# PG03_Analog_Digital_Inputs.net
KiCad netlist of a schematic drawn in Altium Designer
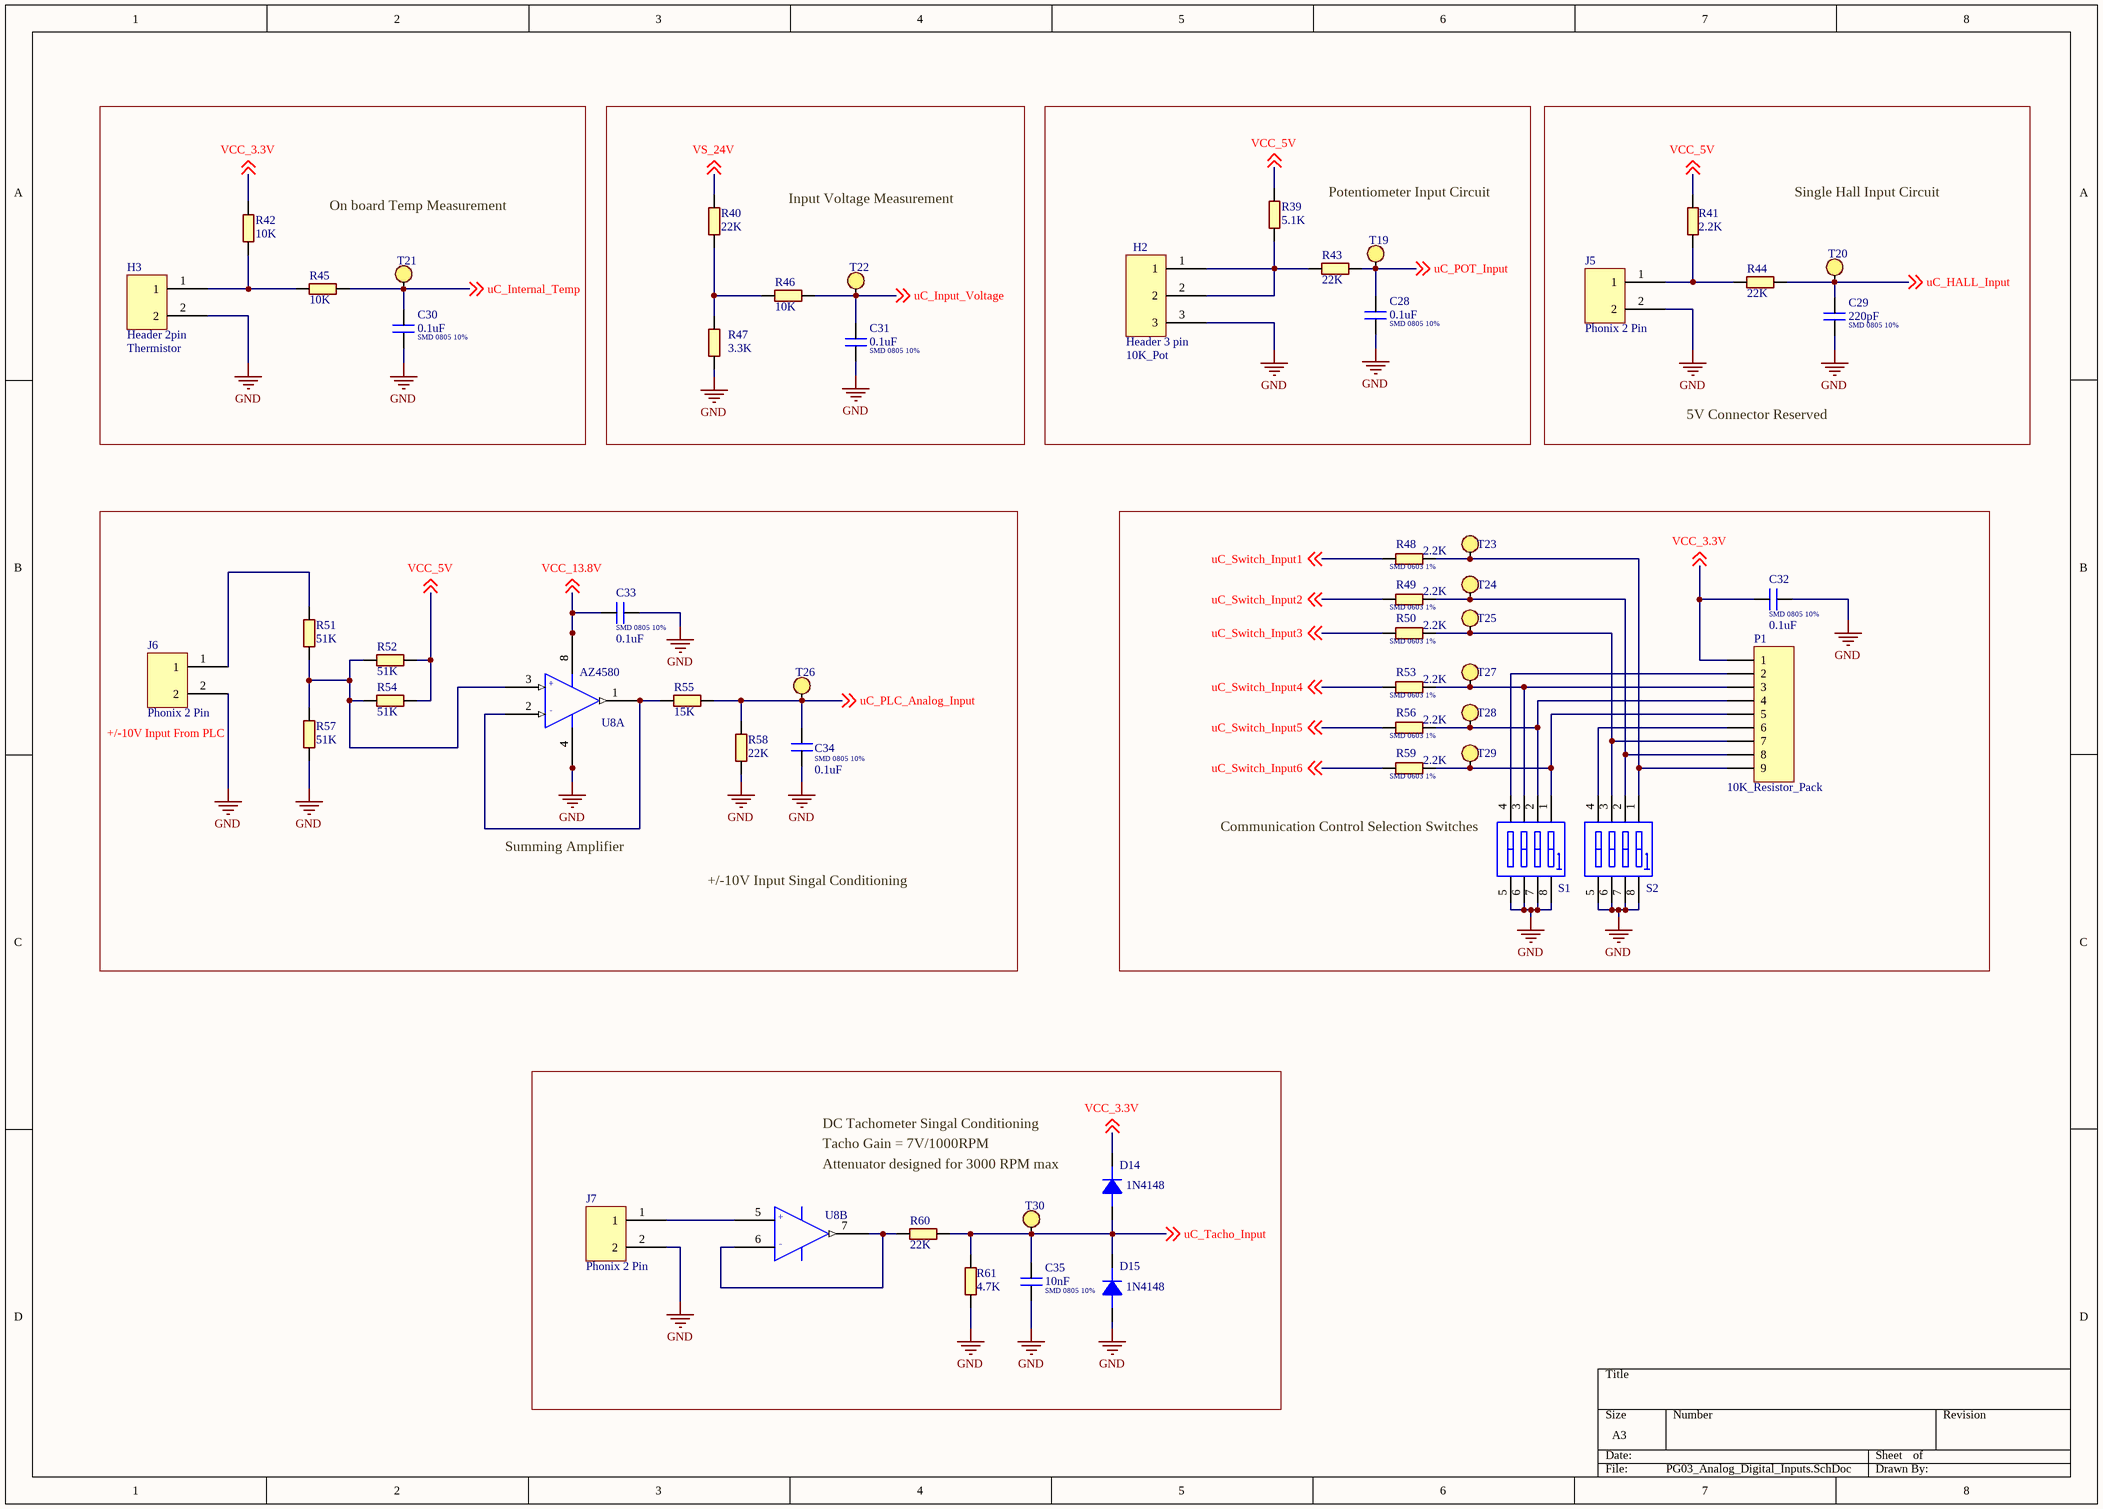
[diagram p0: PG03_Analog_Digital_Inputs.SchDoc]

(export (version "E")
  (design (tool "Eeschema 10.0.6"))
  (components
    (comp (ref "C28")
      (value "SMD 0805 10%")
      (footprint "SMD0805")
      (fields (field (name "MANUFACTURER") "Vishay") (field (name "ALTIUM_VALUE") "0.1uF"))
      (libsource (lib "Schlib1") (part "CAP_SMD"))
    )
    (comp (ref "C29")
      (value "SMD 0805 10%")
      (footprint "SMD0805")
      (fields (field (name "MANUFACTURER") "Vishay") (field (name "ALTIUM_VALUE") "220pF"))
      (libsource (lib "Schlib1") (part "CAP_SMD"))
    )
    (comp (ref "C30")
      (value "SMD 0805 10%")
      (footprint "SMD0805")
      (fields (field (name "MANUFACTURER") "Vishay") (field (name "ALTIUM_VALUE") "0.1uF"))
      (libsource (lib "Schlib1") (part "CAP_SMD"))
    )
    (comp (ref "C31")
      (value "SMD 0805 10%")
      (footprint "SMD0805")
      (fields (field (name "MANUFACTURER") "Vishay") (field (name "ALTIUM_VALUE") "0.1uF"))
      (libsource (lib "Schlib1") (part "CAP_SMD"))
    )
    (comp (ref "C32")
      (value "SMD 0805 10%")
      (footprint "SMD0805")
      (fields (field (name "MANUFACTURER") "Vishay") (field (name "ALTIUM_VALUE") "0.1uF"))
      (libsource (lib "Schlib1") (part "CAP_SMD"))
    )
    (comp (ref "C33")
      (value "SMD 0805 10%")
      (footprint "SMD0805")
      (fields (field (name "MANUFACTURER") "Vishay") (field (name "ALTIUM_VALUE") "0.1uF"))
      (libsource (lib "Schlib1") (part "CAP_SMD"))
    )
    (comp (ref "C34")
      (value "SMD 0805 10%")
      (footprint "SMD0805")
      (fields (field (name "MANUFACTURER") "Vishay") (field (name "ALTIUM_VALUE") "0.1uF"))
      (libsource (lib "Schlib1") (part "CAP_SMD"))
    )
    (comp (ref "C35")
      (value "SMD 0805 10%")
      (footprint "SMD0805")
      (fields (field (name "MANUFACTURER") "Vishay") (field (name "ALTIUM_VALUE") "10nF"))
      (libsource (lib "Schlib1") (part "CAP_SMD"))
    )
    (comp (ref "D14")
      (value "1N4148")
      (fields
        (field (name "PART NO.") "SM4007")
        (field (name "TOLERANCE") "10%")
        (field (name "MANUFACTURER") "Vishay")
      )
      (libsource (lib "*") (part "1N4148"))
    )
    (comp (ref "D15")
      (value "1N4148")
      (fields
        (field (name "PART NO.") "SM4007")
        (field (name "TOLERANCE") "10%")
        (field (name "MANUFACTURER") "Vishay")
      )
      (libsource (lib "*") (part "1N4148"))
    )
    (comp (ref "H2")
      (value "10K_Pot")
      (footprint "Header-3-Pin")
      (fields (field (name "ALTIUM_VALUE") "Header 3 pin"))
      (libsource (lib "Schlib1") (part "Header_3_Pin"))
    )
    (comp (ref "H3")
      (value "Thermistor")
      (footprint "Header-2-Pin")
      (fields (field (name "ALTIUM_VALUE") "Header 2pin"))
      (libsource (lib "Schlib1") (part "Header_2_Pin"))
    )
    (comp (ref "J5")
      (value "Phonix 2 Pin")
      (footprint "PHONIX2")
      (libsource (lib "Schlib1") (part "Phonix_2_Pin"))
    )
    (comp (ref "J6")
      (value "Phonix 2 Pin")
      (footprint "PHONIX2")
      (libsource (lib "Schlib1") (part "Phonix_2_Pin"))
    )
    (comp (ref "J7")
      (value "Phonix 2 Pin")
      (footprint "PHONIX2")
      (libsource (lib "Schlib1") (part "Phonix_2_Pin"))
    )
    (comp (ref "P1")
      (value "10K_Resistor_Pack")
      (footprint "HDR1X9")
      (description "Header, 9-Pin")
      (fields (field (name "PUBLISHER") "Altium Limited"))
      (libsource (lib "Miscellaneous Connectors") (part "Header 9"))
    )
    (comp (ref "R39")
      (value "5.1K")
      (footprint "SMD1206")
      (description "SMD1206  1% Resistor")
      (fields (field (name "MANUFACTURER") "Vishay") (field (name "Comment") "SMD 1206 1%"))
      (libsource (lib "") (part "RES_SMD_1"))
    )
    (comp (ref "R40")
      (value "22K")
      (footprint "SMD1206")
      (description "SMD1206  1% Resistor")
      (fields (field (name "MANUFACTURER") "Vishay") (field (name "Comment") "SMD 1206 1%"))
      (libsource (lib "") (part "RES_SMD_1"))
    )
    (comp (ref "R41")
      (value "2.2K")
      (footprint "SMD1206")
      (description "SMD1206  1% Resistor")
      (fields (field (name "MANUFACTURER") "Vishay") (field (name "Comment") "SMD 1206 1%"))
      (libsource (lib "") (part "RES_SMD_3"))
    )
    (comp (ref "R42")
      (value "10K")
      (footprint "SMD1206")
      (description "SMD1206  1% Resistor")
      (fields (field (name "MANUFACTURER") "Vishay") (field (name "Comment") "SMD 1206 1%"))
      (libsource (lib "") (part "RES_SMD_1"))
    )
    (comp (ref "R43")
      (value "22K")
      (footprint "SMD1206")
      (description "SMD1206  1% Resistor")
      (fields (field (name "MANUFACTURER") "Vishay") (field (name "Comment") "SMD 1206 1%"))
      (libsource (lib "") (part "RES_SMD_2"))
    )
    (comp (ref "R44")
      (value "22K")
      (footprint "SMD1206")
      (description "SMD1206  1% Resistor")
      (fields (field (name "MANUFACTURER") "Vishay") (field (name "Comment") "SMD 1206 1%"))
      (libsource (lib "") (part "RES_SMD_2"))
    )
    (comp (ref "R45")
      (value "10K")
      (footprint "SMD1206")
      (description "SMD1206  1% Resistor")
      (fields (field (name "MANUFACTURER") "Vishay") (field (name "Comment") "SMD 1206 1%"))
      (libsource (lib "") (part "RES_SMD_2"))
    )
    (comp (ref "R46")
      (value "10K")
      (footprint "SMD1206")
      (description "SMD1206  1% Resistor")
      (fields (field (name "MANUFACTURER") "Vishay") (field (name "Comment") "SMD 1206 1%"))
      (libsource (lib "") (part "RES_SMD_2"))
    )
    (comp (ref "R47")
      (value "3.3K")
      (footprint "SMD1206")
      (description "SMD1206  1% Resistor")
      (fields (field (name "MANUFACTURER") "Vishay") (field (name "Comment") "SMD 1206 1%"))
      (libsource (lib "") (part "RES_SMD_3"))
    )
    (comp (ref "R48")
      (value "SMD 0603 1%")
      (footprint "SMD0603")
      (description "SMD1206  1% Resistor")
      (fields (field (name "MANUFACTURER") "Vishay") (field (name "ALTIUM_VALUE") "2.2K"))
      (libsource (lib "Schlib1") (part "RES_SMD"))
    )
    (comp (ref "R49")
      (value "SMD 0603 1%")
      (footprint "SMD0603")
      (description "SMD1206  1% Resistor")
      (fields (field (name "MANUFACTURER") "Vishay") (field (name "ALTIUM_VALUE") "2.2K"))
      (libsource (lib "Schlib1") (part "RES_SMD"))
    )
    (comp (ref "R50")
      (value "SMD 0603 1%")
      (footprint "SMD0603")
      (description "SMD1206  1% Resistor")
      (fields (field (name "MANUFACTURER") "Vishay") (field (name "ALTIUM_VALUE") "2.2K"))
      (libsource (lib "Schlib1") (part "RES_SMD"))
    )
    (comp (ref "R51")
      (value "51K")
      (footprint "SMD1206")
      (description "SMD1206  1% Resistor")
      (fields (field (name "MANUFACTURER") "Vishay") (field (name "Comment") "SMD 1206 1%"))
      (libsource (lib "") (part "RES_SMD_1"))
    )
    (comp (ref "R52")
      (value "51K")
      (footprint "SMD1206")
      (description "SMD1206  1% Resistor")
      (fields (field (name "MANUFACTURER") "Vishay") (field (name "Comment") "SMD 1206 1%"))
      (libsource (lib "") (part "RES_SMD_2"))
    )
    (comp (ref "R53")
      (value "SMD 0603 1%")
      (footprint "SMD0603")
      (description "SMD1206  1% Resistor")
      (fields (field (name "MANUFACTURER") "Vishay") (field (name "ALTIUM_VALUE") "2.2K"))
      (libsource (lib "Schlib1") (part "RES_SMD"))
    )
    (comp (ref "R54")
      (value "51K")
      (footprint "SMD1206")
      (description "SMD1206  1% Resistor")
      (fields (field (name "MANUFACTURER") "Vishay") (field (name "Comment") "SMD 1206 1%"))
      (libsource (lib "") (part "RES_SMD_2"))
    )
    (comp (ref "R55")
      (value "15K")
      (footprint "SMD1206")
      (description "SMD1206  1% Resistor")
      (fields (field (name "MANUFACTURER") "Vishay") (field (name "Comment") "SMD 1206 1%"))
      (libsource (lib "") (part "RES_SMD_2"))
    )
    (comp (ref "R56")
      (value "SMD 0603 1%")
      (footprint "SMD0603")
      (description "SMD1206  1% Resistor")
      (fields (field (name "MANUFACTURER") "Vishay") (field (name "ALTIUM_VALUE") "2.2K"))
      (libsource (lib "Schlib1") (part "RES_SMD"))
    )
    (comp (ref "R57")
      (value "51K")
      (footprint "SMD1206")
      (description "SMD1206  1% Resistor")
      (fields (field (name "MANUFACTURER") "Vishay") (field (name "Comment") "SMD 1206 1%"))
      (libsource (lib "") (part "RES_SMD_1"))
    )
    (comp (ref "R58")
      (value "22K")
      (footprint "SMD1206")
      (description "SMD1206  1% Resistor")
      (fields (field (name "MANUFACTURER") "Vishay") (field (name "Comment") "SMD 1206 1%"))
      (libsource (lib "") (part "RES_SMD_1"))
    )
    (comp (ref "R59")
      (value "SMD 0603 1%")
      (footprint "SMD0603")
      (description "SMD1206  1% Resistor")
      (fields (field (name "MANUFACTURER") "Vishay") (field (name "ALTIUM_VALUE") "2.2K"))
      (libsource (lib "Schlib1") (part "RES_SMD"))
    )
    (comp (ref "R60")
      (value "22K")
      (footprint "SMD1206")
      (description "SMD1206  1% Resistor")
      (fields (field (name "MANUFACTURER") "Vishay") (field (name "Comment") "SMD 1206 1%"))
      (libsource (lib "") (part "RES_SMD_2"))
    )
    (comp (ref "R61")
      (value "4.7K")
      (footprint "SMD1206")
      (description "SMD1206  1% Resistor")
      (fields (field (name "MANUFACTURER") "Vishay") (field (name "Comment") "SMD 1206 1%"))
      (libsource (lib "") (part "RES_SMD_3"))
    )
    (comp (ref "S1")
      (value "2.54mm DIP-4 SMD")
      (footprint "DIP8")
      (description "DIP Switch, 4 Position, SPST")
      (fields (field (name "PUBLISHER") "Altium Limited"))
      (libsource (lib "Miscellaneous Devices") (part "SW DIP-4"))
    )
    (comp (ref "S2")
      (value "2.54mm DIP-4 SMD")
      (footprint "DIP8")
      (description "DIP Switch, 4 Position, SPST")
      (fields (field (name "PUBLISHER") "Altium Limited"))
      (libsource (lib "Miscellaneous Devices") (part "SW DIP-4"))
    )
    (comp (ref "T19")
      (value "Through hole TestPoint")
      (footprint "TP")
      (libsource (lib "Schlib1") (part "TestPoint_TH"))
    )
    (comp (ref "T20")
      (value "Through hole TestPoint")
      (footprint "TP")
      (libsource (lib "Schlib1") (part "TestPoint_TH"))
    )
    (comp (ref "T21")
      (value "Through hole TestPoint")
      (footprint "TP")
      (libsource (lib "Schlib1") (part "TestPoint_TH"))
    )
    (comp (ref "T22")
      (value "Through hole TestPoint")
      (footprint "TP")
      (libsource (lib "Schlib1") (part "TestPoint_TH"))
    )
    (comp (ref "T23")
      (value "Through hole TestPoint")
      (footprint "TP")
      (libsource (lib "Schlib1") (part "TestPoint_TH"))
    )
    (comp (ref "T24")
      (value "Through hole TestPoint")
      (footprint "TP")
      (libsource (lib "Schlib1") (part "TestPoint_TH"))
    )
    (comp (ref "T25")
      (value "Through hole TestPoint")
      (footprint "TP")
      (libsource (lib "Schlib1") (part "TestPoint_TH"))
    )
    (comp (ref "T26")
      (value "Through hole TestPoint")
      (footprint "TP")
      (libsource (lib "Schlib1") (part "TestPoint_TH"))
    )
    (comp (ref "T27")
      (value "Through hole TestPoint")
      (footprint "TP")
      (libsource (lib "Schlib1") (part "TestPoint_TH"))
    )
    (comp (ref "T28")
      (value "Through hole TestPoint")
      (footprint "TP")
      (libsource (lib "Schlib1") (part "TestPoint_TH"))
    )
    (comp (ref "T29")
      (value "Through hole TestPoint")
      (footprint "TP")
      (libsource (lib "Schlib1") (part "TestPoint_TH"))
    )
    (comp (ref "T30")
      (value "Through hole TestPoint")
      (footprint "TP")
      (libsource (lib "Schlib1") (part "TestPoint_TH"))
    )
    (comp (ref "U8")
      (value "AZ4580")
      (footprint "SOIC-8")
      (fields (field (name "MANUFACTURER") "ST Semiconductor") (field (name "Comment") "LM358"))
      (libsource (lib "*") (part "LM358"))
    )
  )
  (nets
    (net (code "1") (name "GND") (class "Default")
      (node (ref "C28") (pin "2") (pinfunction "2_2") (pintype "passive"))
      (node (ref "C29") (pin "2") (pinfunction "2_2") (pintype "passive"))
      (node (ref "C30") (pin "2") (pinfunction "2_2") (pintype "passive"))
      (node (ref "C31") (pin "2") (pinfunction "2_2") (pintype "passive"))
      (node (ref "C32") (pin "2") (pinfunction "2_2") (pintype "passive"))
      (node (ref "C33") (pin "2") (pinfunction "2_2") (pintype "passive"))
      (node (ref "C34") (pin "1") (pinfunction "1_1") (pintype "passive"))
      (node (ref "C35") (pin "2") (pinfunction "2_2") (pintype "passive"))
      (node (ref "D15") (pin "1") (pinfunction "ANODE_1") (pintype "passive"))
      (node (ref "H2") (pin "3") (pinfunction "3_3") (pintype "passive"))
      (node (ref "H3") (pin "2") (pinfunction "2_2") (pintype "passive"))
      (node (ref "J5") (pin "2") (pinfunction "2_2") (pintype "passive"))
      (node (ref "J6") (pin "2") (pinfunction "2_2") (pintype "passive"))
      (node (ref "J7") (pin "2") (pinfunction "2_2") (pintype "passive"))
      (node (ref "R47") (pin "2") (pinfunction "2_2") (pintype "passive"))
      (node (ref "R57") (pin "1") (pinfunction "1_1") (pintype "passive"))
      (node (ref "R58") (pin "1") (pinfunction "1_1") (pintype "passive"))
      (node (ref "R61") (pin "2") (pinfunction "2_2") (pintype "passive"))
      (node (ref "S1") (pin "5") (pinfunction "B4_5") (pintype "passive"))
      (node (ref "S1") (pin "6") (pinfunction "B3_6") (pintype "passive"))
      (node (ref "S1") (pin "7") (pinfunction "B2_7") (pintype "passive"))
      (node (ref "S1") (pin "8") (pinfunction "B1_8") (pintype "passive"))
      (node (ref "S2") (pin "5") (pinfunction "B4_5") (pintype "passive"))
      (node (ref "S2") (pin "6") (pinfunction "B3_6") (pintype "passive"))
      (node (ref "S2") (pin "7") (pinfunction "B2_7") (pintype "passive"))
      (node (ref "S2") (pin "8") (pinfunction "B1_8") (pintype "passive"))
      (node (ref "U8") (pin "4") (pinfunction "GND_4") (pintype "power_in"))
    )
    (net (code "2") (name "Net-(H2-Pad1)") (class "Default")
      (node (ref "H2") (pin "1") (pinfunction "1_1") (pintype "passive"))
      (node (ref "H2") (pin "2") (pinfunction "2_2") (pintype "passive"))
      (node (ref "R39") (pin "1") (pinfunction "1_1") (pintype "passive"))
      (node (ref "R43") (pin "2") (pinfunction "2_2") (pintype "passive"))
    )
    (net (code "3") (name "Net-(H3-Pad1)") (class "Default")
      (node (ref "H3") (pin "1") (pinfunction "1_1") (pintype "passive"))
      (node (ref "R42") (pin "1") (pinfunction "1_1") (pintype "passive"))
      (node (ref "R45") (pin "2") (pinfunction "2_2") (pintype "passive"))
    )
    (net (code "4") (name "Net-(J5-Pad1)") (class "Default")
      (node (ref "J5") (pin "1") (pinfunction "1_1") (pintype "passive"))
      (node (ref "R41") (pin "2") (pinfunction "2_2") (pintype "passive"))
      (node (ref "R44") (pin "2") (pinfunction "2_2") (pintype "passive"))
    )
    (net (code "5") (name "Net-(J6-Pad1)") (class "Default")
      (node (ref "J6") (pin "1") (pinfunction "1_1") (pintype "passive"))
      (node (ref "R51") (pin "2") (pinfunction "2_2") (pintype "passive"))
    )
    (net (code "6") (name "Net-(R40-Pad1)") (class "Default")
      (node (ref "R40") (pin "1") (pinfunction "1_1") (pintype "passive"))
      (node (ref "R46") (pin "2") (pinfunction "2_2") (pintype "passive"))
      (node (ref "R47") (pin "1") (pinfunction "1_1") (pintype "passive"))
    )
    (net (code "7") (name "Net-(S1-A1)") (class "Default")
      (node (ref "P1") (pin "5") (pinfunction "5_5") (pintype "passive"))
      (node (ref "R59") (pin "2") (pinfunction "2_2") (pintype "passive"))
      (node (ref "S1") (pin "1") (pinfunction "A1_1") (pintype "passive"))
      (node (ref "T29") (pin "1") (pintype "passive"))
    )
    (net (code "8") (name "Net-(S1-A2)") (class "Default")
      (node (ref "P1") (pin "4") (pinfunction "4_4") (pintype "passive"))
      (node (ref "R56") (pin "2") (pinfunction "2_2") (pintype "passive"))
      (node (ref "S1") (pin "2") (pinfunction "A2_2") (pintype "passive"))
      (node (ref "T28") (pin "1") (pintype "passive"))
    )
    (net (code "9") (name "Net-(S1-A3)") (class "Default")
      (node (ref "P1") (pin "3") (pinfunction "3_3") (pintype "passive"))
      (node (ref "R53") (pin "2") (pinfunction "2_2") (pintype "passive"))
      (node (ref "S1") (pin "3") (pinfunction "A3_3") (pintype "passive"))
      (node (ref "T27") (pin "1") (pintype "passive"))
    )
    (net (code "10") (name "Net-(S1-A4)") (class "Default")
      (node (ref "P1") (pin "2") (pinfunction "2_2") (pintype "passive"))
      (node (ref "S1") (pin "4") (pinfunction "A4_4") (pintype "passive"))
    )
    (net (code "11") (name "Net-(S2-A1)") (class "Default")
      (node (ref "P1") (pin "9") (pinfunction "9_9") (pintype "passive"))
      (node (ref "R48") (pin "2") (pinfunction "2_2") (pintype "passive"))
      (node (ref "S2") (pin "1") (pinfunction "A1_1") (pintype "passive"))
      (node (ref "T23") (pin "1") (pintype "passive"))
    )
    (net (code "12") (name "Net-(S2-A2)") (class "Default")
      (node (ref "P1") (pin "8") (pinfunction "8_8") (pintype "passive"))
      (node (ref "R49") (pin "2") (pinfunction "2_2") (pintype "passive"))
      (node (ref "S2") (pin "2") (pinfunction "A2_2") (pintype "passive"))
      (node (ref "T24") (pin "1") (pintype "passive"))
    )
    (net (code "13") (name "Net-(S2-A3)") (class "Default")
      (node (ref "P1") (pin "7") (pinfunction "7_7") (pintype "passive"))
      (node (ref "R50") (pin "2") (pinfunction "2_2") (pintype "passive"))
      (node (ref "S2") (pin "3") (pinfunction "A3_3") (pintype "passive"))
      (node (ref "T25") (pin "1") (pintype "passive"))
    )
    (net (code "14") (name "Net-(S2-A4)") (class "Default")
      (node (ref "P1") (pin "6") (pinfunction "6_6") (pintype "passive"))
      (node (ref "S2") (pin "4") (pinfunction "A4_4") (pintype "passive"))
    )
    (net (code "15") (name "Net-(U8A-+IN)") (class "Default")
      (node (ref "R51") (pin "1") (pinfunction "1_1") (pintype "passive"))
      (node (ref "R52") (pin "2") (pinfunction "2_2") (pintype "passive"))
      (node (ref "R54") (pin "2") (pinfunction "2_2") (pintype "passive"))
      (node (ref "R57") (pin "2") (pinfunction "2_2") (pintype "passive"))
      (node (ref "U8") (pin "3") (pinfunction "+IN_3") (pintype "input"))
    )
    (net (code "16") (name "Net-(U8A--IN)") (class "Default")
      (node (ref "R55") (pin "2") (pinfunction "2_2") (pintype "passive"))
      (node (ref "U8") (pin "1") (pinfunction "OUT_1") (pintype "output"))
      (node (ref "U8") (pin "2") (pinfunction "-IN_2") (pintype "input"))
    )
    (net (code "17") (name "Net-(U8B-+IN)") (class "Default")
      (node (ref "J7") (pin "1") (pinfunction "1_1") (pintype "passive"))
      (node (ref "U8") (pin "5") (pinfunction "+IN_5") (pintype "passive"))
    )
    (net (code "18") (name "Net-(U8B--IN)") (class "Default")
      (node (ref "R60") (pin "2") (pinfunction "2_2") (pintype "passive"))
      (node (ref "U8") (pin "6") (pinfunction "-IN_6") (pintype "passive"))
      (node (ref "U8") (pin "7") (pinfunction "OUT_7") (pintype "output"))
    )
    (net (code "19") (name "VCC_3.3V") (class "Default")
      (node (ref "C32") (pin "1") (pinfunction "1_1") (pintype "passive"))
      (node (ref "D14") (pin "2") (pinfunction "CATHODE_2") (pintype "passive"))
      (node (ref "P1") (pin "1") (pinfunction "1_1") (pintype "passive"))
      (node (ref "R42") (pin "2") (pinfunction "2_2") (pintype "passive"))
    )
    (net (code "20") (name "VCC_5V") (class "Default")
      (node (ref "R39") (pin "2") (pinfunction "2_2") (pintype "passive"))
      (node (ref "R41") (pin "1") (pinfunction "1_1") (pintype "passive"))
      (node (ref "R52") (pin "1") (pinfunction "1_1") (pintype "passive"))
      (node (ref "R54") (pin "1") (pinfunction "1_1") (pintype "passive"))
    )
    (net (code "21") (name "VCC_13.8V") (class "Default")
      (node (ref "C33") (pin "1") (pinfunction "1_1") (pintype "passive"))
      (node (ref "U8") (pin "8") (pinfunction "VCC_8") (pintype "power_in"))
    )
    (net (code "22") (name "VS_24V") (class "Default")
      (node (ref "R40") (pin "2") (pinfunction "2_2") (pintype "passive"))
    )
    (net (code "23") (name "uC_HALL_Input") (class "Default")
      (node (ref "C29") (pin "1") (pinfunction "1_1") (pintype "passive"))
      (node (ref "R44") (pin "1") (pinfunction "1_1") (pintype "passive"))
      (node (ref "T20") (pin "1") (pintype "passive"))
    )
    (net (code "24") (name "uC_Input_Voltage") (class "Default")
      (node (ref "C31") (pin "1") (pinfunction "1_1") (pintype "passive"))
      (node (ref "R46") (pin "1") (pinfunction "1_1") (pintype "passive"))
      (node (ref "T22") (pin "1") (pintype "passive"))
    )
    (net (code "25") (name "uC_Internal_Temp") (class "Default")
      (node (ref "C30") (pin "1") (pinfunction "1_1") (pintype "passive"))
      (node (ref "R45") (pin "1") (pinfunction "1_1") (pintype "passive"))
      (node (ref "T21") (pin "1") (pintype "passive"))
    )
    (net (code "26") (name "uC_PLC_Analog_Input") (class "Default")
      (node (ref "C34") (pin "2") (pinfunction "2_2") (pintype "passive"))
      (node (ref "R55") (pin "1") (pinfunction "1_1") (pintype "passive"))
      (node (ref "R58") (pin "2") (pinfunction "2_2") (pintype "passive"))
      (node (ref "T26") (pin "1") (pintype "passive"))
    )
    (net (code "27") (name "uC_POT_Input") (class "Default")
      (node (ref "C28") (pin "1") (pinfunction "1_1") (pintype "passive"))
      (node (ref "R43") (pin "1") (pinfunction "1_1") (pintype "passive"))
      (node (ref "T19") (pin "1") (pintype "passive"))
    )
    (net (code "28") (name "uC_Switch_Input1") (class "Default")
      (node (ref "R48") (pin "1") (pinfunction "1_1") (pintype "passive"))
    )
    (net (code "29") (name "uC_Switch_Input2") (class "Default")
      (node (ref "R49") (pin "1") (pinfunction "1_1") (pintype "passive"))
    )
    (net (code "30") (name "uC_Switch_Input3") (class "Default")
      (node (ref "R50") (pin "1") (pinfunction "1_1") (pintype "passive"))
    )
    (net (code "31") (name "uC_Switch_Input4") (class "Default")
      (node (ref "R53") (pin "1") (pinfunction "1_1") (pintype "passive"))
    )
    (net (code "32") (name "uC_Switch_Input5") (class "Default")
      (node (ref "R56") (pin "1") (pinfunction "1_1") (pintype "passive"))
    )
    (net (code "33") (name "uC_Switch_Input6") (class "Default")
      (node (ref "R59") (pin "1") (pinfunction "1_1") (pintype "passive"))
    )
    (net (code "34") (name "uC_Tacho_Input") (class "Default")
      (node (ref "C35") (pin "1") (pinfunction "1_1") (pintype "passive"))
      (node (ref "D14") (pin "1") (pinfunction "ANODE_1") (pintype "passive"))
      (node (ref "D15") (pin "2") (pinfunction "CATHODE_2") (pintype "passive"))
      (node (ref "R60") (pin "1") (pinfunction "1_1") (pintype "passive"))
      (node (ref "R61") (pin "1") (pinfunction "1_1") (pintype "passive"))
      (node (ref "T30") (pin "1") (pintype "passive"))
    )
  )
)
